# USB.net
KiCad netlist of a schematic drawn in Altium Designer
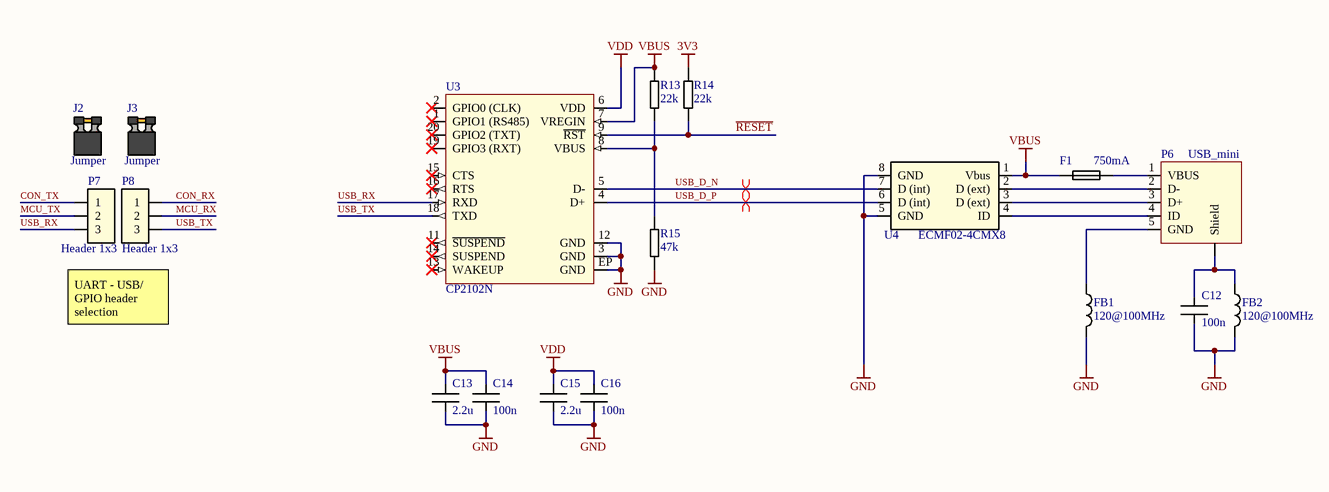
[diagram p0: USB.SchDoc]

(export (version "E")
  (design (tool "Eeschema 10.0.6"))
  (components
    (comp (ref "C12")
      (value "100n")
      (footprint "CAPC1005N")
      (description "0402 SMD Capacitor")
      (fields (field (name "TOLERANCE") "10%"))
      (libsource (lib "RLC") (part "Capacitor"))
    )
    (comp (ref "C13")
      (value "2.2u")
      (footprint "CAPC1005N")
      (description "0402 SMD Capacitor")
      (fields (field (name "TOLERANCE") "10%") (field (name "Comment") "Capacitor"))
      (libsource (lib "RLC") (part "Capacitor"))
    )
    (comp (ref "C14")
      (value "100n")
      (footprint "CAPC1005N")
      (description "0402 SMD Capacitor")
      (fields (field (name "TOLERANCE") "10%"))
      (libsource (lib "RLC") (part "Capacitor"))
    )
    (comp (ref "C15")
      (value "2.2u")
      (footprint "CAPC1005N")
      (description "0402 SMD Capacitor")
      (fields (field (name "TOLERANCE") "10%") (field (name "Comment") "Capacitor"))
      (libsource (lib "RLC") (part "Capacitor"))
    )
    (comp (ref "C16")
      (value "100n")
      (footprint "CAPC1005N")
      (description "0402 SMD Capacitor")
      (fields (field (name "TOLERANCE") "10%"))
      (libsource (lib "RLC") (part "Capacitor"))
    )
    (comp (ref "F1")
      (value "PTC Fuse")
      (footprint "RESC2012N")
      (description "PTC Fuse 500mA")
      (fields (field (name "STAND CURRENT") "750mA"))
      (libsource (lib "PTC_Fuse") (part "SD075-16"))
    )
    (comp (ref "FB1")
      (value "120@100MHz")
      (footprint "INDC1005N")
      (description "Ferrite Bead")
      (fields (field (name "TOLERANCE") "25%"))
      (libsource (lib "RLC") (part "Inductor"))
    )
    (comp (ref "FB2")
      (value "120@100MHz")
      (footprint "INDC1005N")
      (description "Ferrite Bead")
      (fields (field (name "TOLERANCE") "25%"))
      (libsource (lib "RLC") (part "Inductor"))
    )
    (comp (ref "J2")
      (value "Jumper")
      (footprint "JUMPER-B")
      (description "1x2, 2.54mm Black header jumper")
      (libsource (lib "Ninigi_Jumpers") (part "Header Jumper Black"))
    )
    (comp (ref "J3")
      (value "Jumper")
      (footprint "JUMPER-B")
      (description "1x2, 2.54mm Black header jumper")
      (libsource (lib "Ninigi_Jumpers") (part "Header Jumper Black"))
    )
    (comp (ref "P6")
      (value "USB_mini")
      (footprint "MUSB-B5-S-RA-TSMT-CS1")
      (description "Gniazdo; USB B mini; SMT; poziome; V: USB 2.0; złocony")
      (libsource (lib "Adam Tech Connectors") (part "MUSB-B5-S-RA-TSMT-CS1"))
    )
    (comp (ref "P7")
      (value "Header 1x3")
      (footprint "Header 1x3, Male, 2.54mm, Straight, THT")
      (description "Pin header, 1x3, 2.54mm")
      (libsource (lib "") (part "Header 1x3_1"))
    )
    (comp (ref "P8")
      (value "Header 1x3")
      (footprint "Header 1x3, Male, 2.54mm, Straight, THT")
      (description "Pin header, 1x3, 2.54mm")
      (libsource (lib "Header") (part "Header 1x3"))
    )
    (comp (ref "R13")
      (value "22k")
      (footprint "RESC1005N")
      (description "0402 Film SMD Resistor")
      (fields (field (name "TOLERANCE") "1%") (field (name "POWER") "0.1W"))
      (libsource (lib "RLC") (part "Resistor"))
    )
    (comp (ref "R14")
      (value "22k")
      (footprint "RESC1005N")
      (description "0402 Film SMD Resistor")
      (fields (field (name "TOLERANCE") "1%") (field (name "POWER") "0.1W"))
      (libsource (lib "RLC") (part "Resistor"))
    )
    (comp (ref "R15")
      (value "47k")
      (footprint "RESC1005N")
      (description "0402 Film SMD Resistor")
      (fields (field (name "TOLERANCE") "1%") (field (name "POWER") "0.1W"))
      (libsource (lib "RLC") (part "Resistor"))
    )
    (comp (ref "U3")
      (value "CP2102N")
      (footprint "QFN-20")
      (description "USB Interface IC USBXpress - USB to UART Bridge QFN20")
      (libsource (lib "SiliconLabs") (part "CP2102N"))
    )
    (comp (ref "U4")
      (value "ECMF02-4CMX8")
      (footprint "uQFN-8")
      (description "STMicroelectronics Common Mode Filter with ESD protection, USB compatible")
      (libsource (lib "STMicroelectronics_Protective") (part "ECMF02-4CMX8"))
    )
  )
  (nets
    (net (code "1") (name "/CON_RX") (class "Default")
      (node (ref "P8") (pin "1") (pinfunction "1_1") (pintype "passive"))
    )
    (net (code "2") (name "/CON_TX") (class "Default")
      (node (ref "P7") (pin "1") (pinfunction "1_1") (pintype "passive"))
    )
    (net (code "3") (name "/MCU_RX") (class "Default")
      (node (ref "P8") (pin "2") (pinfunction "2_2") (pintype "passive"))
    )
    (net (code "4") (name "/MCU_TX") (class "Default")
      (node (ref "P7") (pin "2") (pinfunction "2_2") (pintype "passive"))
    )
    (net (code "5") (name "/USB_D_N") (class "Default")
      (node (ref "U3") (pin "5") (pinfunction "D-_5") (pintype "bidirectional"))
      (node (ref "U4") (pin "7") (pinfunction "D_(int)_7") (pintype "passive"))
    )
    (net (code "6") (name "/USB_D_P") (class "Default")
      (node (ref "U3") (pin "4") (pinfunction "D+_4") (pintype "bidirectional"))
      (node (ref "U4") (pin "6") (pinfunction "D_(int)_6") (pintype "passive"))
    )
    (net (code "7") (name "/USB_RX") (class "Default")
      (node (ref "P7") (pin "3") (pinfunction "3_3") (pintype "passive"))
      (node (ref "U3") (pin "17") (pinfunction "RXD_17") (pintype "input"))
    )
    (net (code "8") (name "/USB_TX") (class "Default")
      (node (ref "P8") (pin "3") (pinfunction "3_3") (pintype "passive"))
      (node (ref "U3") (pin "18") (pinfunction "TXD_18") (pintype "output"))
    )
    (net (code "9") (name "/~{RESET}") (class "Default")
      (node (ref "R14") (pin "1") (pinfunction "1_1") (pintype "passive"))
      (node (ref "U3") (pin "9") (pinfunction "~{RST}_9") (pintype "input"))
    )
    (net (code "10") (name "3V3") (class "Default")
      (node (ref "R14") (pin "2") (pinfunction "2_2") (pintype "passive"))
    )
    (net (code "11") (name "GND") (class "Default")
      (node (ref "C12") (pin "1") (pinfunction "1_1") (pintype "passive"))
      (node (ref "C13") (pin "1") (pinfunction "1_1") (pintype "passive"))
      (node (ref "C14") (pin "1") (pinfunction "1_1") (pintype "passive"))
      (node (ref "C15") (pin "1") (pinfunction "1_1") (pintype "passive"))
      (node (ref "C16") (pin "1") (pinfunction "1_1") (pintype "passive"))
      (node (ref "FB1") (pin "2") (pinfunction "2_2") (pintype "passive"))
      (node (ref "FB2") (pin "2") (pinfunction "2_2") (pintype "passive"))
      (node (ref "R15") (pin "1") (pinfunction "1_1") (pintype "passive"))
      (node (ref "U3") (pin "12") (pinfunction "GND_12") (pintype "power_in"))
      (node (ref "U3") (pin "3") (pinfunction "GND_3") (pintype "power_in"))
      (node (ref "U3") (pin "EP") (pinfunction "GND_EP") (pintype "power_in"))
      (node (ref "U4") (pin "5") (pinfunction "GND_5") (pintype "passive"))
      (node (ref "U4") (pin "8") (pinfunction "GND_8") (pintype "passive"))
    )
    (net (code "12") (name "Net-(P6-D+)") (class "Default")
      (node (ref "P6") (pin "3") (pinfunction "D+_3") (pintype "bidirectional"))
      (node (ref "U4") (pin "3") (pinfunction "D_(ext)_3") (pintype "passive"))
    )
    (net (code "13") (name "Net-(P6-D-)") (class "Default")
      (node (ref "P6") (pin "2") (pinfunction "D-_2") (pintype "bidirectional"))
      (node (ref "U4") (pin "2") (pinfunction "D_(ext)_2") (pintype "passive"))
    )
    (net (code "14") (name "Net-(P6-GND)") (class "Default")
      (node (ref "FB1") (pin "1") (pinfunction "1_1") (pintype "passive"))
      (node (ref "P6") (pin "5") (pinfunction "GND_5") (pintype "power_in"))
    )
    (net (code "15") (name "Net-(P6-ID)") (class "Default")
      (node (ref "P6") (pin "4") (pinfunction "ID_4") (pintype "bidirectional"))
      (node (ref "U4") (pin "4") (pinfunction "ID_4") (pintype "passive"))
    )
    (net (code "16") (name "Net-(P6-Shield)") (class "Default")
      (node (ref "C12") (pin "2") (pinfunction "2_2") (pintype "passive"))
      (node (ref "FB2") (pin "1") (pinfunction "1_1") (pintype "passive"))
      (node (ref "P6") (pin "0") (pinfunction "Shield_0") (pintype "passive"))
    )
    (net (code "17") (name "Net-(P6-VBUS)") (class "Default")
      (node (ref "F1") (pin "2") (pinfunction "2_2") (pintype "passive"))
      (node (ref "P6") (pin "1") (pinfunction "VBUS_1") (pintype "power_in"))
    )
    (net (code "18") (name "Net-(U3-VBUS)") (class "Default")
      (node (ref "R13") (pin "1") (pinfunction "1_1") (pintype "passive"))
      (node (ref "R15") (pin "2") (pinfunction "2_2") (pintype "passive"))
      (node (ref "U3") (pin "8") (pinfunction "VBUS_8") (pintype "input"))
    )
    (net (code "19") (name "VBUS") (class "Default")
      (node (ref "C13") (pin "2") (pinfunction "2_2") (pintype "passive"))
      (node (ref "C14") (pin "2") (pinfunction "2_2") (pintype "passive"))
      (node (ref "F1") (pin "1") (pinfunction "1_1") (pintype "passive"))
      (node (ref "R13") (pin "2") (pinfunction "2_2") (pintype "passive"))
      (node (ref "U3") (pin "7") (pinfunction "VREGIN_7") (pintype "input"))
      (node (ref "U4") (pin "1") (pinfunction "Vbus_1") (pintype "passive"))
    )
    (net (code "20") (name "VDD") (class "Default")
      (node (ref "C15") (pin "2") (pinfunction "2_2") (pintype "passive"))
      (node (ref "C16") (pin "2") (pinfunction "2_2") (pintype "passive"))
      (node (ref "U3") (pin "6") (pinfunction "VDD_6") (pintype "power_in"))
    )
    (net (code "21") (name "unconnected-(U3-CTS-Pad15)") (class "Default")
      (node (ref "U3") (pin "15") (pinfunction "CTS_15") (pintype "input+no_connect"))
    )
    (net (code "22") (name "unconnected-(U3-GPIO0_(CLK)-Pad2)") (class "Default")
      (node (ref "U3") (pin "2") (pinfunction "GPIO0_(CLK)_2") (pintype "bidirectional+no_connect"))
    )
    (net (code "23") (name "unconnected-(U3-GPIO1_(RS485)-Pad1)") (class "Default")
      (node (ref "U3") (pin "1") (pinfunction "GPIO1_(RS485)_1") (pintype "bidirectional+no_connect"))
    )
    (net (code "24") (name "unconnected-(U3-GPIO2_(TXT)-Pad20)") (class "Default")
      (node (ref "U3") (pin "20") (pinfunction "GPIO2_(TXT)_20") (pintype "bidirectional+no_connect"))
    )
    (net (code "25") (name "unconnected-(U3-GPIO3_(RXT)-Pad19)") (class "Default")
      (node (ref "U3") (pin "19") (pinfunction "GPIO3_(RXT)_19") (pintype "bidirectional+no_connect"))
    )
    (net (code "26") (name "unconnected-(U3-RTS-Pad16)") (class "Default")
      (node (ref "U3") (pin "16") (pinfunction "RTS_16") (pintype "output+no_connect"))
    )
    (net (code "27") (name "unconnected-(U3-SUSPEND-Pad14)") (class "Default")
      (node (ref "U3") (pin "14") (pinfunction "SUSPEND_14") (pintype "output+no_connect"))
    )
    (net (code "28") (name "unconnected-(U3-WAKEUP-Pad13)") (class "Default")
      (node (ref "U3") (pin "13") (pinfunction "WAKEUP_13") (pintype "input+no_connect"))
    )
    (net (code "29") (name "unconnected-(U3-~{SUSPEND}-Pad11)") (class "Default")
      (node (ref "U3") (pin "11") (pinfunction "~{SUSPEND}_11") (pintype "output+no_connect"))
    )
  )
)
